# openSX70_MEROE_V7_20190603.net
KiCad netlist of a schematic drawn in EAGLE
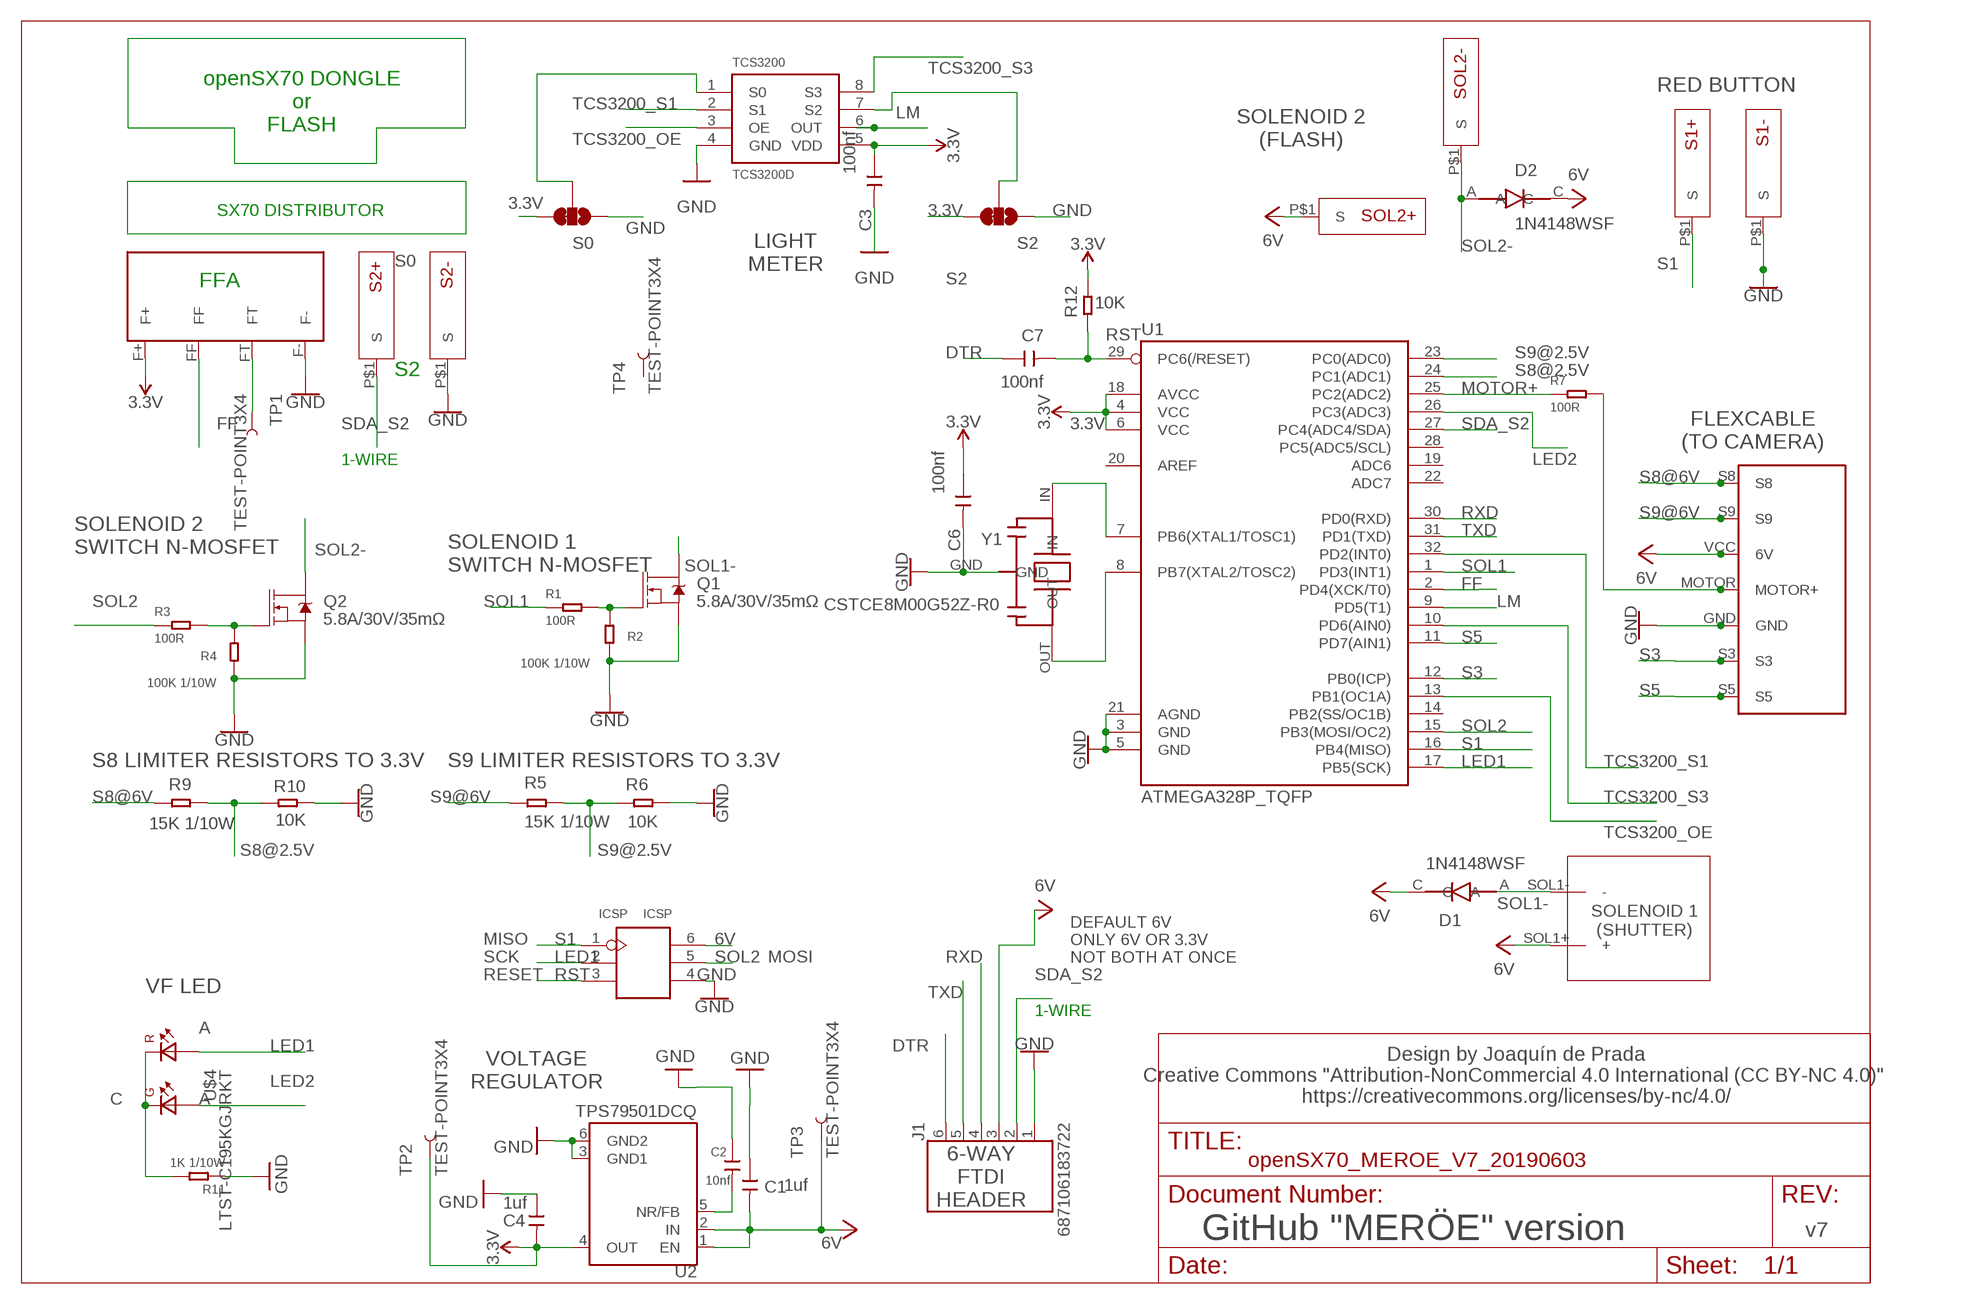
[diagram p0: schematic, sheet 1]

(export (version "E")
  (design (tool "Eeschema 10.0.6"))
  (components
    (comp (ref "C1")
      (value "1uf")
      (footprint "eagle-import:C0603")
      (fields (field (name "MPN") "CC0603KRX5R6BB106"))
      (libsource (lib "eagle-import") (part "CERAMIC-10UF-10V-10%-X5R(0603)"))
    )
    (comp (ref "C2")
      (value "10nf")
      (footprint "eagle-import:C0603")
      (fields (field (name "MPN") "CC0603KRX7R9BB104"))
      (libsource (lib "eagle-import") (part "CERAMIC-100NF-50V-10%-X7R(0603)"))
    )
    (comp (ref "C3")
      (value "100nf")
      (footprint "eagle-import:C0603")
      (fields (field (name "MPN") "CC0603KRX7R9BB104"))
      (libsource (lib "eagle-import") (part "CERAMIC-100NF-50V-10%-X7R(0603)"))
    )
    (comp (ref "C4")
      (value "1uf")
      (footprint "eagle-import:C0603")
      (fields (field (name "MPN") "CC0603KRX5R6BB106"))
      (libsource (lib "eagle-import") (part "CERAMIC-10UF-10V-10%-X5R(0603)"))
    )
    (comp (ref "C6")
      (value "100nf")
      (footprint "eagle-import:C0603")
      (fields (field (name "MPN") "CC0603KRX7R9BB104"))
      (libsource (lib "eagle-import") (part "CERAMIC-100NF-50V-10%-X7R(0603)"))
    )
    (comp (ref "C7")
      (value "100nf")
      (footprint "eagle-import:C0603")
      (fields (field (name "MPN") "CC0603KRX7R9BB104"))
      (libsource (lib "eagle-import") (part "CERAMIC-100NF-50V-10%-X7R(0603)"))
    )
    (comp (ref "D1")
      (value "1N4148WSF")
      (footprint "eagle-import:SODFL2512X100N")
      (fields (field (name "MANUFACTURER") "Fairchild Semiconductor"))
      (libsource (lib "eagle-import") (part "1N4148WS"))
    )
    (comp (ref "D2")
      (value "1N4148WSF")
      (footprint "eagle-import:SODFL2512X100N")
      (fields (field (name "MANUFACTURER") "Fairchild Semiconductor"))
      (libsource (lib "eagle-import") (part "1N4148WS"))
    )
    (comp (ref "ICSP")
      (value "ICSP")
      (footprint "eagle-import:H2X3-2.54")
      (libsource (lib "eagle-import") (part "ICSP"))
    )
    (comp (ref "J1")
      (value "687106183722")
      (footprint "eagle-import:687106183722")
      (fields (field (name "MF") "Wurth Electronics"))
      (libsource (lib "eagle-import") (part "687106183722"))
    )
    (comp (ref "Q1")
      (value "5.8A/30V/35mΩ")
      (footprint "eagle-import:SOT23-3")
      (libsource (lib "eagle-import") (part "MOSFET-NCH-AO3404A"))
    )
    (comp (ref "Q2")
      (value "5.8A/30V/35mΩ")
      (footprint "eagle-import:SOT23-3")
      (libsource (lib "eagle-import") (part "MOSFET-NCH-AO3404A"))
    )
    (comp (ref "R1")
      (value "100R")
      (footprint "eagle-import:R0603")
      (fields (field (name "MPN") "RC0603JR-07100RL"))
      (libsource (lib "eagle-import") (part "SMD-RES-100R-5%-1/10W(0603)"))
    )
    (comp (ref "R2")
      (value "100K 1/10W")
      (footprint "eagle-import:R0603")
      (fields (field (name "MPN") "RC0603JR-07100KL"))
      (libsource (lib "eagle-import") (part "SMD-RES-100K-5%-1/10W(0603)"))
    )
    (comp (ref "R3")
      (value "100R")
      (footprint "eagle-import:R0603")
      (fields (field (name "MPN") "RC0603JR-07100RL"))
      (libsource (lib "eagle-import") (part "SMD-RES-100R-5%-1/10W(0603)"))
    )
    (comp (ref "R4")
      (value "100K 1/10W")
      (footprint "eagle-import:R0603")
      (fields (field (name "MPN") "RC0603JR-07100KL"))
      (libsource (lib "eagle-import") (part "SMD-RES-100K-5%-1/10W(0603)"))
    )
    (comp (ref "R5")
      (value "15K 1/10W")
      (footprint "eagle-import:R0603")
      (fields (field (name "MPN") "RC0603FR-0715KL"))
      (libsource (lib "eagle-import") (part "SMD-RES-15K-1%-1/10W(0603)"))
    )
    (comp (ref "R6")
      (value "10K")
      (footprint "eagle-import:R0603")
      (fields (field (name "MPN") "RC0603FR-0710KL"))
      (libsource (lib "eagle-import") (part "SMD-RES-10K-1%-1/10W(0603)"))
    )
    (comp (ref "R7")
      (value "100R")
      (footprint "eagle-import:R0603")
      (fields (field (name "MPN") "RC0603JR-07100RL"))
      (libsource (lib "eagle-import") (part "SMD-RES-100R-5%-1/10W(0603)"))
    )
    (comp (ref "R9")
      (value "15K 1/10W")
      (footprint "eagle-import:R0603")
      (fields (field (name "MPN") "RC0603FR-0715KL"))
      (libsource (lib "eagle-import") (part "SMD-RES-15K-1%-1/10W(0603)"))
    )
    (comp (ref "R10")
      (value "10K")
      (footprint "eagle-import:R0603")
      (fields (field (name "MPN") "RC0603FR-0710KL"))
      (libsource (lib "eagle-import") (part "SMD-RES-10K-1%-1/10W(0603)"))
    )
    (comp (ref "R11")
      (value "1K 1/10W")
      (footprint "eagle-import:R0603")
      (fields (field (name "MPN") "RC0603JR-071KL"))
      (libsource (lib "eagle-import") (part "SMD-RES-1K-5%-1/10W(0603)"))
    )
    (comp (ref "R12")
      (value "10K")
      (footprint "eagle-import:R0603")
      (fields (field (name "MPN") "RC0603FR-0710KL"))
      (libsource (lib "eagle-import") (part "SMD-RES-10K-1%-1/10W(0603)"))
    )
    (comp (ref "S0")
      (value "S0")
      (footprint "eagle-import:SMT-JUMPER_3_1-NC_TRACE_SILK")
      (libsource (lib "eagle-import") (part "JUMPER-SMT_3_1-NC_TRACE_SILK"))
    )
    (comp (ref "S1+")
      (value "SX70-S-PAD-NEW")
      (footprint "eagle-import:SX70-S-PAD2")
      (libsource (lib "eagle-import") (part "SX70-S-PAD-NEW"))
    )
    (comp (ref "S1-")
      (value "SX70-S-PAD-NEW")
      (footprint "eagle-import:SX70-S-PAD2")
      (libsource (lib "eagle-import") (part "SX70-S-PAD-NEW"))
    )
    (comp (ref "S2")
      (value "S2")
      (footprint "eagle-import:SMT-JUMPER_3_1-NC_TRACE_SILK")
      (libsource (lib "eagle-import") (part "JUMPER-SMT_3_1-NC_TRACE_SILK"))
    )
    (comp (ref "S2+")
      (value "SX70-S-PAD-NEW")
      (footprint "eagle-import:SX70-S-PAD2")
      (libsource (lib "eagle-import") (part "SX70-S-PAD-NEW"))
    )
    (comp (ref "S2-")
      (value "SX70-S-PAD-NEW")
      (footprint "eagle-import:SX70-S-PAD2")
      (libsource (lib "eagle-import") (part "SX70-S-PAD-NEW"))
    )
    (comp (ref "SOL1")
      (value "SX70-SOLENOID1-2PADS")
      (footprint "eagle-import:SX70-SOLENOID1-2")
      (libsource (lib "eagle-import") (part "SX70-SOLENOID1-2PADS"))
    )
    (comp (ref "SOL2+")
      (value "SX70-S-PAD-NEW")
      (footprint "eagle-import:SX70-S-PAD2")
      (libsource (lib "eagle-import") (part "SX70-S-PAD-NEW"))
    )
    (comp (ref "SOL2-")
      (value "SX70-S-PAD-NEW")
      (footprint "eagle-import:SX70-S-PAD2")
      (libsource (lib "eagle-import") (part "SX70-S-PAD-NEW"))
    )
    (comp (ref "TCS3200")
      (value "TCS3200D")
      (footprint "eagle-import:SOIC8")
      (fields (field (name "MF") "ams") (field (name "MP") "TCS3200D-TR"))
      (libsource (lib "eagle-import") (part "TCS3200D"))
    )
    (comp (ref "TP1")
      (value "TEST-POINT3X4")
      (footprint "eagle-import:PAD.03X.04")
      (libsource (lib "eagle-import") (part "TEST-POINT3X4"))
    )
    (comp (ref "TP2")
      (value "TEST-POINT3X4")
      (footprint "eagle-import:PAD.03X.04")
      (libsource (lib "eagle-import") (part "TEST-POINT3X4"))
    )
    (comp (ref "TP3")
      (value "TEST-POINT3X4")
      (footprint "eagle-import:PAD.03X.04")
      (libsource (lib "eagle-import") (part "TEST-POINT3X4"))
    )
    (comp (ref "TP4")
      (value "TEST-POINT3X4")
      (footprint "eagle-import:PAD.03X.04")
      (libsource (lib "eagle-import") (part "TEST-POINT3X4"))
    )
    (comp (ref "U$1")
      (value "SX70-7-PAD")
      (footprint "eagle-import:SX70-7-PAD-PROPER")
      (libsource (lib "eagle-import") (part "SX70-7-PAD"))
    )
    (comp (ref "U$2")
      (value "FFA")
      (footprint "eagle-import:FFA-PAD-PACKAGE")
      (libsource (lib "eagle-import") (part "SX70-FFA-PAD"))
    )
    (comp (ref "U$4")
      (value "LTST-C195KGJRKT")
      (footprint "eagle-import:LTST-BILED-15X16")
      (fields (field (name "MF") "Lite-On Inc."))
      (libsource (lib "eagle-import") (part "LTST-C195KGJRKT"))
    )
    (comp (ref "U1")
      (value "ATMEGA328P_TQFP")
      (footprint "eagle-import:TQFP32-08")
      (libsource (lib "eagle-import") (part "ATMEGA328P_TQFP"))
    )
    (comp (ref "U2")
      (value "TPS79501DCQ")
      (footprint "eagle-import:SOT127P706X180-6N")
      (fields (field (name "MF") "Texas Instruments"))
      (libsource (lib "eagle-import") (part "TPS79501DCQ"))
    )
    (comp (ref "Y1")
      (value "CSTCE8M00G52Z-R0")
      (footprint "eagle-import:CFP95P160X100-3N")
      (fields (field (name "MF") "Murata") (field (name "MP") "CSTCE16M0V53-R0"))
      (libsource (lib "eagle-import") (part "CSTCE16M0V53-R0"))
    )
  )
  (nets
    (net (code "1") (name "/DTR") (class "Default")
      (node (ref "C7") (pin "1") (pinfunction "1_1") (pintype "passive"))
      (node (ref "J1") (pin "6") (pinfunction "1_6") (pintype "passive"))
    )
    (net (code "2") (name "/FF") (class "Default")
      (node (ref "U$2") (pin "FF") (pinfunction "FF_FF") (pintype "bidirectional"))
      (node (ref "U1") (pin "2") (pinfunction "PD4(XCK/T0)_2") (pintype "bidirectional"))
    )
    (net (code "3") (name "/LED1") (class "Default")
      (node (ref "ICSP") (pin "2") (pinfunction "SCK_2") (pintype "bidirectional"))
      (node (ref "U$4") (pin "P$2") (pinfunction "A2_P$2") (pintype "passive"))
      (node (ref "U1") (pin "17") (pinfunction "PB5(SCK)_17") (pintype "bidirectional"))
    )
    (net (code "4") (name "/LED2") (class "Default")
      (node (ref "U$4") (pin "P$1") (pinfunction "A1_P$1") (pintype "passive"))
      (node (ref "U1") (pin "26") (pinfunction "PC3(ADC3)_26") (pintype "bidirectional"))
    )
    (net (code "5") (name "/LM") (class "Default")
      (node (ref "TCS3200") (pin "6") (pinfunction "OUT_6") (pintype "bidirectional"))
      (node (ref "U1") (pin "9") (pinfunction "PD5(T1)_9") (pintype "bidirectional"))
    )
    (net (code "6") (name "/MOTOR+") (class "Default")
      (node (ref "R7") (pin "1") (pinfunction "1_1") (pintype "passive"))
      (node (ref "U1") (pin "25") (pinfunction "PC2(ADC2)_25") (pintype "bidirectional"))
    )
    (net (code "7") (name "/RST") (class "Default")
      (node (ref "C7") (pin "2") (pinfunction "2_2") (pintype "passive"))
      (node (ref "ICSP") (pin "3") (pinfunction "RST_3") (pintype "bidirectional"))
      (node (ref "R12") (pin "1") (pinfunction "1_1") (pintype "passive"))
      (node (ref "U1") (pin "29") (pinfunction "PC6(/RESET)_29") (pintype "bidirectional"))
    )
    (net (code "8") (name "/RXD") (class "Default")
      (node (ref "J1") (pin "4") (pinfunction "3_4") (pintype "passive"))
      (node (ref "U1") (pin "30") (pinfunction "PD0(RXD)_30") (pintype "bidirectional"))
    )
    (net (code "9") (name "/S1") (class "Default")
      (node (ref "ICSP") (pin "1") (pinfunction "MISO_1") (pintype "bidirectional"))
      (node (ref "S1+") (pin "P$1") (pinfunction "S_P$1") (pintype "bidirectional"))
      (node (ref "U1") (pin "16") (pinfunction "PB4(MISO)_16") (pintype "bidirectional"))
    )
    (net (code "10") (name "/S3") (class "Default")
      (node (ref "U$1") (pin "S3") (pinfunction "S3_S3") (pintype "bidirectional"))
      (node (ref "U1") (pin "12") (pinfunction "PB0(ICP)_12") (pintype "bidirectional"))
    )
    (net (code "11") (name "/S5") (class "Default")
      (node (ref "U$1") (pin "S5") (pinfunction "S5_S5") (pintype "bidirectional"))
      (node (ref "U1") (pin "11") (pinfunction "PD7(AIN1)_11") (pintype "bidirectional"))
    )
    (net (code "12") (name "/S8@2.5V") (class "Default")
      (node (ref "R10") (pin "1") (pinfunction "1_1") (pintype "passive"))
      (node (ref "R9") (pin "2") (pinfunction "2_2") (pintype "passive"))
      (node (ref "U1") (pin "24") (pinfunction "PC1(ADC1)_24") (pintype "bidirectional"))
    )
    (net (code "13") (name "/S8@6V") (class "Default")
      (node (ref "R9") (pin "1") (pinfunction "1_1") (pintype "passive"))
      (node (ref "U$1") (pin "S8") (pinfunction "S8_S8") (pintype "bidirectional"))
    )
    (net (code "14") (name "/S9@2.5V") (class "Default")
      (node (ref "R5") (pin "2") (pinfunction "2_2") (pintype "passive"))
      (node (ref "R6") (pin "1") (pinfunction "1_1") (pintype "passive"))
      (node (ref "U1") (pin "23") (pinfunction "PC0(ADC0)_23") (pintype "bidirectional"))
    )
    (net (code "15") (name "/S9@6V") (class "Default")
      (node (ref "R5") (pin "1") (pinfunction "1_1") (pintype "passive"))
      (node (ref "U$1") (pin "S9") (pinfunction "S9_S9") (pintype "bidirectional"))
    )
    (net (code "16") (name "/SDA_S2") (class "Default")
      (node (ref "J1") (pin "2") (pinfunction "5_2") (pintype "passive"))
      (node (ref "S2+") (pin "P$1") (pinfunction "S_P$1") (pintype "bidirectional"))
      (node (ref "U1") (pin "27") (pinfunction "PC4(ADC4/SDA)_27") (pintype "bidirectional"))
    )
    (net (code "17") (name "/SOL1") (class "Default")
      (node (ref "R1") (pin "1") (pinfunction "1_1") (pintype "passive"))
      (node (ref "U1") (pin "1") (pinfunction "PD3(INT1)_1") (pintype "bidirectional"))
    )
    (net (code "18") (name "/SOL1-") (class "Default")
      (node (ref "D1") (pin "A") (pinfunction "A_A") (pintype "passive"))
      (node (ref "Q1") (pin "3") (pinfunction "D_3") (pintype "bidirectional"))
      (node (ref "SOL1") (pin "SOL1-") (pinfunction "-_SOL1-") (pintype "bidirectional"))
    )
    (net (code "19") (name "/SOL2") (class "Default")
      (node (ref "ICSP") (pin "5") (pinfunction "MOSI_5") (pintype "bidirectional"))
      (node (ref "R3") (pin "1") (pinfunction "1_1") (pintype "passive"))
      (node (ref "U1") (pin "15") (pinfunction "PB3(MOSI/OC2)_15") (pintype "bidirectional"))
    )
    (net (code "20") (name "/SOL2-") (class "Default")
      (node (ref "D2") (pin "A") (pinfunction "A_A") (pintype "passive"))
      (node (ref "Q2") (pin "3") (pinfunction "D_3") (pintype "bidirectional"))
      (node (ref "SOL2-") (pin "P$1") (pinfunction "S_P$1") (pintype "bidirectional"))
    )
    (net (code "21") (name "/TCS3200_OE") (class "Default")
      (node (ref "TCS3200") (pin "3") (pinfunction "OE_3") (pintype "bidirectional"))
      (node (ref "U1") (pin "13") (pinfunction "PB1(OC1A)_13") (pintype "bidirectional"))
    )
    (net (code "22") (name "/TCS3200_S1") (class "Default")
      (node (ref "TCS3200") (pin "2") (pinfunction "S1_2") (pintype "bidirectional"))
      (node (ref "U1") (pin "32") (pinfunction "PD2(INT0)_32") (pintype "bidirectional"))
    )
    (net (code "23") (name "/TCS3200_S3") (class "Default")
      (node (ref "TCS3200") (pin "8") (pinfunction "S3_8") (pintype "bidirectional"))
      (node (ref "U1") (pin "10") (pinfunction "PD6(AIN0)_10") (pintype "bidirectional"))
    )
    (net (code "24") (name "/TXD") (class "Default")
      (node (ref "J1") (pin "5") (pinfunction "2_5") (pintype "passive"))
      (node (ref "U1") (pin "31") (pinfunction "PD1(TXD)_31") (pintype "bidirectional"))
    )
    (net (code "25") (name "3.3V") (class "Default")
      (node (ref "C3") (pin "1") (pinfunction "1_1") (pintype "passive"))
      (node (ref "C4") (pin "2") (pinfunction "2_2") (pintype "passive"))
      (node (ref "C6") (pin "1") (pinfunction "1_1") (pintype "passive"))
      (node (ref "R12") (pin "2") (pinfunction "2_2") (pintype "passive"))
      (node (ref "S0") (pin "3") (pinfunction "3_3") (pintype "passive"))
      (node (ref "S2") (pin "3") (pinfunction "3_3") (pintype "passive"))
      (node (ref "TCS3200") (pin "5") (pinfunction "VDD_5") (pintype "bidirectional"))
      (node (ref "TP2") (pin "P$1") (pinfunction "1_P$1") (pintype "bidirectional"))
      (node (ref "U$2") (pin "F+") (pinfunction "F+_F+") (pintype "bidirectional"))
      (node (ref "U1") (pin "18") (pinfunction "AVCC_18") (pintype "bidirectional"))
      (node (ref "U1") (pin "4") (pinfunction "VCC_4") (pintype "bidirectional"))
      (node (ref "U1") (pin "6") (pinfunction "VCC_6") (pintype "bidirectional"))
      (node (ref "U2") (pin "4") (pinfunction "OUT_4") (pintype "output"))
    )
    (net (code "26") (name "6V") (class "Default")
      (node (ref "C1") (pin "2") (pinfunction "2_2") (pintype "passive"))
      (node (ref "D1") (pin "C") (pinfunction "C_C") (pintype "passive"))
      (node (ref "D2") (pin "C") (pinfunction "C_C") (pintype "passive"))
      (node (ref "ICSP") (pin "6") (pinfunction "VCC_6") (pintype "bidirectional"))
      (node (ref "J1") (pin "3") (pinfunction "4_3") (pintype "passive"))
      (node (ref "SOL1") (pin "SOL1+") (pinfunction "+_SOL1+") (pintype "bidirectional"))
      (node (ref "SOL2+") (pin "P$1") (pinfunction "S_P$1") (pintype "bidirectional"))
      (node (ref "TP3") (pin "P$1") (pinfunction "1_P$1") (pintype "bidirectional"))
      (node (ref "U$1") (pin "VCC") (pinfunction "6V_VCC") (pintype "bidirectional"))
      (node (ref "U2") (pin "1") (pinfunction "EN_1") (pintype "input"))
      (node (ref "U2") (pin "2") (pinfunction "IN_2") (pintype "input"))
    )
    (net (code "27") (name "GND") (class "Default")
      (node (ref "C1") (pin "1") (pinfunction "1_1") (pintype "passive"))
      (node (ref "C2") (pin "1") (pinfunction "1_1") (pintype "passive"))
      (node (ref "C3") (pin "2") (pinfunction "2_2") (pintype "passive"))
      (node (ref "C4") (pin "1") (pinfunction "1_1") (pintype "passive"))
      (node (ref "C6") (pin "2") (pinfunction "2_2") (pintype "passive"))
      (node (ref "ICSP") (pin "4") (pinfunction "GND_4") (pintype "bidirectional"))
      (node (ref "J1") (pin "1") (pinfunction "6_1") (pintype "passive"))
      (node (ref "Q1") (pin "2") (pinfunction "S_2") (pintype "bidirectional"))
      (node (ref "Q2") (pin "2") (pinfunction "S_2") (pintype "bidirectional"))
      (node (ref "R10") (pin "2") (pinfunction "2_2") (pintype "passive"))
      (node (ref "R11") (pin "1") (pinfunction "1_1") (pintype "passive"))
      (node (ref "R2") (pin "1") (pinfunction "1_1") (pintype "passive"))
      (node (ref "R4") (pin "1") (pinfunction "1_1") (pintype "passive"))
      (node (ref "R6") (pin "2") (pinfunction "2_2") (pintype "passive"))
      (node (ref "S0") (pin "1") (pinfunction "1_1") (pintype "passive"))
      (node (ref "S1-") (pin "P$1") (pinfunction "S_P$1") (pintype "bidirectional"))
      (node (ref "S2") (pin "1") (pinfunction "1_1") (pintype "passive"))
      (node (ref "S2-") (pin "P$1") (pinfunction "S_P$1") (pintype "bidirectional"))
      (node (ref "TCS3200") (pin "4") (pinfunction "GND_4") (pintype "bidirectional"))
      (node (ref "U$1") (pin "GND") (pinfunction "GND_GND") (pintype "bidirectional"))
      (node (ref "U$2") (pin "F-") (pinfunction "F-_F-") (pintype "bidirectional"))
      (node (ref "U1") (pin "21") (pinfunction "AGND_21") (pintype "bidirectional"))
      (node (ref "U1") (pin "3") (pinfunction "GND_3") (pintype "bidirectional"))
      (node (ref "U1") (pin "5") (pinfunction "GND_5") (pintype "bidirectional"))
      (node (ref "U2") (pin "3") (pinfunction "GND1_3") (pintype "power_in"))
      (node (ref "U2") (pin "6") (pinfunction "GND2_6") (pintype "power_in"))
      (node (ref "Y1") (pin "GND") (pinfunction "GND_GND") (pintype "passive"))
    )
    (net (code "28") (name "Net-(Q1-G)") (class "Default")
      (node (ref "Q1") (pin "1") (pinfunction "G_1") (pintype "bidirectional"))
      (node (ref "R1") (pin "2") (pinfunction "2_2") (pintype "passive"))
      (node (ref "R2") (pin "2") (pinfunction "2_2") (pintype "passive"))
    )
    (net (code "29") (name "Net-(Q2-G)") (class "Default")
      (node (ref "Q2") (pin "1") (pinfunction "G_1") (pintype "bidirectional"))
      (node (ref "R3") (pin "2") (pinfunction "2_2") (pintype "passive"))
      (node (ref "R4") (pin "2") (pinfunction "2_2") (pintype "passive"))
    )
    (net (code "30") (name "Net-(TCS3200-S0)") (class "Default")
      (node (ref "S0") (pin "2") (pinfunction "2_2") (pintype "passive"))
      (node (ref "TCS3200") (pin "1") (pinfunction "S0_1") (pintype "bidirectional"))
    )
    (net (code "31") (name "Net-(TCS3200-S2)") (class "Default")
      (node (ref "S2") (pin "2") (pinfunction "2_2") (pintype "passive"))
      (node (ref "TCS3200") (pin "7") (pinfunction "S2_7") (pintype "bidirectional"))
    )
    (net (code "32") (name "Net-(TP1-1)") (class "Default")
      (node (ref "TP1") (pin "P$1") (pinfunction "1_P$1") (pintype "bidirectional"))
      (node (ref "U$2") (pin "FT") (pinfunction "FT_FT") (pintype "bidirectional"))
    )
    (net (code "33") (name "Net-(U$1-MOTOR+)") (class "Default")
      (node (ref "R7") (pin "2") (pinfunction "2_2") (pintype "passive"))
      (node (ref "U$1") (pin "MOTOR") (pinfunction "MOTOR+_MOTOR") (pintype "bidirectional"))
    )
    (net (code "34") (name "Net-(U$4-K1)") (class "Default")
      (node (ref "R11") (pin "2") (pinfunction "2_2") (pintype "passive"))
      (node (ref "U$4") (pin "P$3") (pinfunction "K1_P$3") (pintype "passive"))
      (node (ref "U$4") (pin "P$4") (pinfunction "K2_P$4") (pintype "passive"))
    )
    (net (code "35") (name "Net-(U1-PB6(XTAL1{slash}TOSC1))") (class "Default")
      (node (ref "U1") (pin "7") (pinfunction "PB6(XTAL1/TOSC1)_7") (pintype "bidirectional"))
      (node (ref "Y1") (pin "IN") (pinfunction "IN_IN") (pintype "input"))
    )
    (net (code "36") (name "Net-(U1-PB7(XTAL2{slash}TOSC2))") (class "Default")
      (node (ref "U1") (pin "8") (pinfunction "PB7(XTAL2/TOSC2)_8") (pintype "bidirectional"))
      (node (ref "Y1") (pin "OUT") (pinfunction "OUT_OUT") (pintype "output"))
    )
    (net (code "37") (name "Net-(U2-NR{slash}FB)") (class "Default")
      (node (ref "C2") (pin "2") (pinfunction "2_2") (pintype "passive"))
      (node (ref "U2") (pin "5") (pinfunction "NR/FB_5") (pintype "input"))
    )
    (net (code "38") (name "unconnected-(TP4-1-PadP$1)") (class "Default")
      (node (ref "TP4") (pin "P$1") (pinfunction "1_P$1") (pintype "bidirectional"))
    )
    (net (code "39") (name "unconnected-(U1-ADC6-Pad19)") (class "Default")
      (node (ref "U1") (pin "19") (pinfunction "ADC6_19") (pintype "bidirectional"))
    )
    (net (code "40") (name "unconnected-(U1-ADC7-Pad22)") (class "Default")
      (node (ref "U1") (pin "22") (pinfunction "ADC7_22") (pintype "bidirectional"))
    )
    (net (code "41") (name "unconnected-(U1-AREF-Pad20)") (class "Default")
      (node (ref "U1") (pin "20") (pinfunction "AREF_20") (pintype "bidirectional"))
    )
    (net (code "42") (name "unconnected-(U1-PB2(SS{slash}OC1B)-Pad14)") (class "Default")
      (node (ref "U1") (pin "14") (pinfunction "PB2(SS/OC1B)_14") (pintype "bidirectional"))
    )
    (net (code "43") (name "unconnected-(U1-PC5(ADC5{slash}SCL)-Pad28)") (class "Default")
      (node (ref "U1") (pin "28") (pinfunction "PC5(ADC5/SCL)_28") (pintype "bidirectional"))
    )
  )
)
